# MUX.net
KiCad netlist of a schematic drawn in Altium Designer
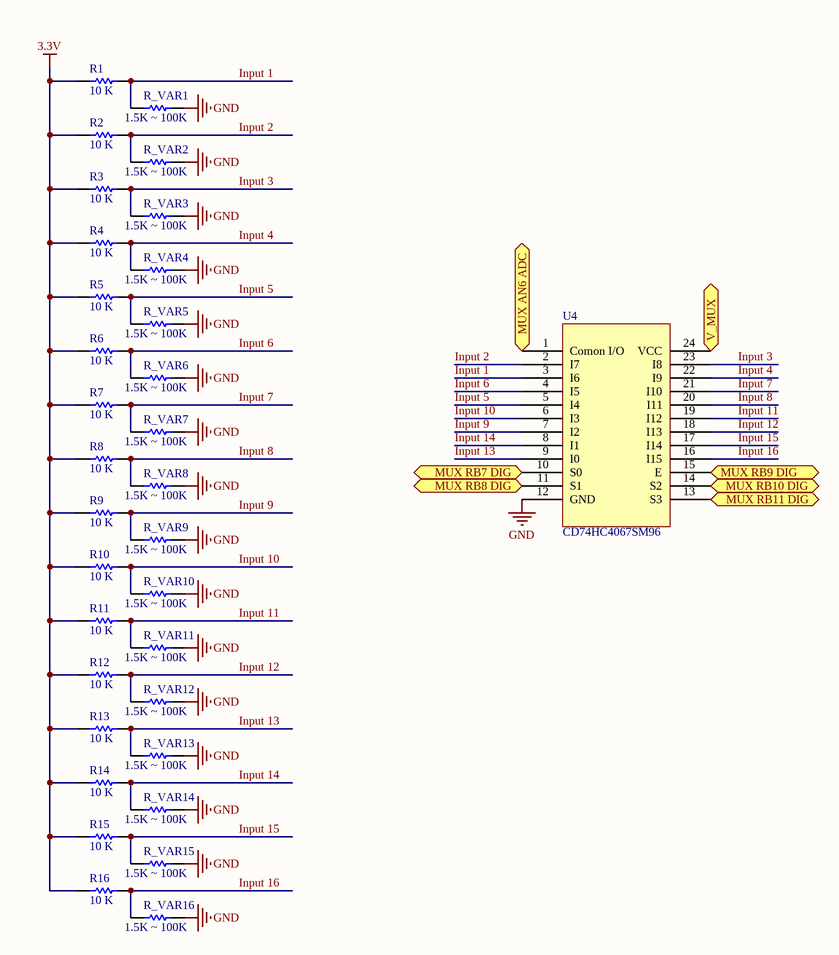
[diagram p0: MUX.SchDoc]

(export (version "E")
  (design (tool "Eeschema 10.0.6"))
  (components
    (comp (ref "R1")
      (value "10 K")
      (footprint "Resistor0603")
      (description "Resistor")
      (fields (field (name "PUBLISHER") "Altium Limited"))
      (libsource (lib "Miscellaneous Devices") (part "Res1"))
    )
    (comp (ref "R2")
      (value "10 K")
      (footprint "Resistor0603")
      (description "Resistor")
      (fields (field (name "PUBLISHER") "Altium Limited"))
      (libsource (lib "Miscellaneous Devices") (part "Res1"))
    )
    (comp (ref "R3")
      (value "10 K")
      (footprint "Resistor0603")
      (description "Resistor")
      (fields (field (name "PUBLISHER") "Altium Limited"))
      (libsource (lib "Miscellaneous Devices") (part "Res1"))
    )
    (comp (ref "R4")
      (value "10 K")
      (footprint "Resistor0603")
      (description "Resistor")
      (fields (field (name "PUBLISHER") "Altium Limited"))
      (libsource (lib "Miscellaneous Devices") (part "Res1"))
    )
    (comp (ref "R5")
      (value "10 K")
      (footprint "Resistor0603")
      (description "Resistor")
      (fields (field (name "PUBLISHER") "Altium Limited"))
      (libsource (lib "Miscellaneous Devices") (part "Res1"))
    )
    (comp (ref "R6")
      (value "10 K")
      (footprint "Resistor0603")
      (description "Resistor")
      (fields (field (name "PUBLISHER") "Altium Limited"))
      (libsource (lib "Miscellaneous Devices") (part "Res1"))
    )
    (comp (ref "R7")
      (value "10 K")
      (footprint "Resistor0603")
      (description "Resistor")
      (fields (field (name "PUBLISHER") "Altium Limited"))
      (libsource (lib "Miscellaneous Devices") (part "Res1"))
    )
    (comp (ref "R8")
      (value "10 K")
      (footprint "Resistor0603")
      (description "Resistor")
      (fields (field (name "PUBLISHER") "Altium Limited"))
      (libsource (lib "Miscellaneous Devices") (part "Res1"))
    )
    (comp (ref "R9")
      (value "10 K")
      (footprint "Resistor0603")
      (description "Resistor")
      (fields (field (name "PUBLISHER") "Altium Limited"))
      (libsource (lib "Miscellaneous Devices") (part "Res1"))
    )
    (comp (ref "R10")
      (value "10 K")
      (footprint "Resistor0603")
      (description "Resistor")
      (fields (field (name "PUBLISHER") "Altium Limited"))
      (libsource (lib "Miscellaneous Devices") (part "Res1"))
    )
    (comp (ref "R11")
      (value "10 K")
      (footprint "Resistor0603")
      (description "Resistor")
      (fields (field (name "PUBLISHER") "Altium Limited"))
      (libsource (lib "Miscellaneous Devices") (part "Res1"))
    )
    (comp (ref "R12")
      (value "10 K")
      (footprint "Resistor0603")
      (description "Resistor")
      (fields (field (name "PUBLISHER") "Altium Limited"))
      (libsource (lib "Miscellaneous Devices") (part "Res1"))
    )
    (comp (ref "R13")
      (value "10 K")
      (footprint "Resistor0603")
      (description "Resistor")
      (fields (field (name "PUBLISHER") "Altium Limited"))
      (libsource (lib "Miscellaneous Devices") (part "Res1"))
    )
    (comp (ref "R14")
      (value "10 K")
      (footprint "Resistor0603")
      (description "Resistor")
      (fields (field (name "PUBLISHER") "Altium Limited"))
      (libsource (lib "Miscellaneous Devices") (part "Res1"))
    )
    (comp (ref "R15")
      (value "10 K")
      (footprint "Resistor0603")
      (description "Resistor")
      (fields (field (name "PUBLISHER") "Altium Limited"))
      (libsource (lib "Miscellaneous Devices") (part "Res1"))
    )
    (comp (ref "R16")
      (value "10 K")
      (footprint "Resistor0603")
      (description "Resistor")
      (fields (field (name "PUBLISHER") "Altium Limited"))
      (libsource (lib "Miscellaneous Devices") (part "Res1"))
    )
    (comp (ref "R_VAR1")
      (value "1.5K ~ 100K")
      (footprint "OrderPiece")
      (description "Resistor")
      (fields (field (name "PUBLISHER") "Altium Limited"))
      (libsource (lib "Miscellaneous Devices") (part "Res1"))
    )
    (comp (ref "R_VAR2")
      (value "1.5K ~ 100K")
      (footprint "OrderPiece")
      (description "Resistor")
      (fields (field (name "PUBLISHER") "Altium Limited"))
      (libsource (lib "Miscellaneous Devices") (part "Res1"))
    )
    (comp (ref "R_VAR3")
      (value "1.5K ~ 100K")
      (footprint "OrderPiece")
      (description "Resistor")
      (fields (field (name "PUBLISHER") "Altium Limited"))
      (libsource (lib "Miscellaneous Devices") (part "Res1"))
    )
    (comp (ref "R_VAR4")
      (value "1.5K ~ 100K")
      (footprint "OrderPiece")
      (description "Resistor")
      (fields (field (name "PUBLISHER") "Altium Limited"))
      (libsource (lib "Miscellaneous Devices") (part "Res1"))
    )
    (comp (ref "R_VAR5")
      (value "1.5K ~ 100K")
      (footprint "OrderPiece")
      (description "Resistor")
      (fields (field (name "PUBLISHER") "Altium Limited"))
      (libsource (lib "Miscellaneous Devices") (part "Res1"))
    )
    (comp (ref "R_VAR6")
      (value "1.5K ~ 100K")
      (footprint "OrderPiece")
      (description "Resistor")
      (fields (field (name "PUBLISHER") "Altium Limited"))
      (libsource (lib "Miscellaneous Devices") (part "Res1"))
    )
    (comp (ref "R_VAR7")
      (value "1.5K ~ 100K")
      (footprint "OrderPiece")
      (description "Resistor")
      (fields (field (name "PUBLISHER") "Altium Limited"))
      (libsource (lib "Miscellaneous Devices") (part "Res1"))
    )
    (comp (ref "R_VAR8")
      (value "1.5K ~ 100K")
      (footprint "OrderPiece")
      (description "Resistor")
      (fields (field (name "PUBLISHER") "Altium Limited"))
      (libsource (lib "Miscellaneous Devices") (part "Res1"))
    )
    (comp (ref "R_VAR9")
      (value "1.5K ~ 100K")
      (footprint "OrderPiece")
      (description "Resistor")
      (fields (field (name "PUBLISHER") "Altium Limited"))
      (libsource (lib "Miscellaneous Devices") (part "Res1"))
    )
    (comp (ref "R_VAR10")
      (value "1.5K ~ 100K")
      (footprint "OrderPiece")
      (description "Resistor")
      (fields (field (name "PUBLISHER") "Altium Limited"))
      (libsource (lib "Miscellaneous Devices") (part "Res1"))
    )
    (comp (ref "R_VAR11")
      (value "1.5K ~ 100K")
      (footprint "OrderPiece")
      (description "Resistor")
      (fields (field (name "PUBLISHER") "Altium Limited"))
      (libsource (lib "Miscellaneous Devices") (part "Res1"))
    )
    (comp (ref "R_VAR12")
      (value "1.5K ~ 100K")
      (footprint "OrderPiece")
      (description "Resistor")
      (fields (field (name "PUBLISHER") "Altium Limited"))
      (libsource (lib "Miscellaneous Devices") (part "Res1"))
    )
    (comp (ref "R_VAR13")
      (value "1.5K ~ 100K")
      (footprint "OrderPiece")
      (description "Resistor")
      (fields (field (name "PUBLISHER") "Altium Limited"))
      (libsource (lib "Miscellaneous Devices") (part "Res1"))
    )
    (comp (ref "R_VAR14")
      (value "1.5K ~ 100K")
      (footprint "OrderPiece")
      (description "Resistor")
      (fields (field (name "PUBLISHER") "Altium Limited"))
      (libsource (lib "Miscellaneous Devices") (part "Res1"))
    )
    (comp (ref "R_VAR15")
      (value "1.5K ~ 100K")
      (footprint "OrderPiece")
      (description "Resistor")
      (fields (field (name "PUBLISHER") "Altium Limited"))
      (libsource (lib "Miscellaneous Devices") (part "Res1"))
    )
    (comp (ref "R_VAR16")
      (value "1.5K ~ 100K")
      (footprint "OrderPiece")
      (description "Resistor")
      (fields (field (name "PUBLISHER") "Altium Limited"))
      (libsource (lib "Miscellaneous Devices") (part "Res1"))
    )
    (comp (ref "U4")
      (value "CD74HC4067SM96")
      (footprint "MUX")
      (libsource (lib "PROBOT_Schema_Library") (part "Analog Multiplexor"))
    )
  )
  (nets
    (net (code "1") (name "/Input 1") (class "Default")
      (node (ref "R1") (pin "2") (pinfunction "2_2") (pintype "passive"))
      (node (ref "R_VAR1") (pin "1") (pinfunction "1_1") (pintype "passive"))
      (node (ref "U4") (pin "3") (pinfunction "I6_3") (pintype "passive"))
    )
    (net (code "2") (name "/Input 2") (class "Default")
      (node (ref "R2") (pin "2") (pinfunction "2_2") (pintype "passive"))
      (node (ref "R_VAR2") (pin "1") (pinfunction "1_1") (pintype "passive"))
      (node (ref "U4") (pin "2") (pinfunction "I7_2") (pintype "passive"))
    )
    (net (code "3") (name "/Input 3") (class "Default")
      (node (ref "R3") (pin "2") (pinfunction "2_2") (pintype "passive"))
      (node (ref "R_VAR3") (pin "1") (pinfunction "1_1") (pintype "passive"))
      (node (ref "U4") (pin "23") (pinfunction "I8_23") (pintype "passive"))
    )
    (net (code "4") (name "/Input 4") (class "Default")
      (node (ref "R4") (pin "2") (pinfunction "2_2") (pintype "passive"))
      (node (ref "R_VAR4") (pin "1") (pinfunction "1_1") (pintype "passive"))
      (node (ref "U4") (pin "22") (pinfunction "I9_22") (pintype "passive"))
    )
    (net (code "5") (name "/Input 5") (class "Default")
      (node (ref "R5") (pin "2") (pinfunction "2_2") (pintype "passive"))
      (node (ref "R_VAR5") (pin "1") (pinfunction "1_1") (pintype "passive"))
      (node (ref "U4") (pin "5") (pinfunction "I4_5") (pintype "passive"))
    )
    (net (code "6") (name "/Input 6") (class "Default")
      (node (ref "R6") (pin "2") (pinfunction "2_2") (pintype "passive"))
      (node (ref "R_VAR6") (pin "1") (pinfunction "1_1") (pintype "passive"))
      (node (ref "U4") (pin "4") (pinfunction "I5_4") (pintype "passive"))
    )
    (net (code "7") (name "/Input 7") (class "Default")
      (node (ref "R7") (pin "2") (pinfunction "2_2") (pintype "passive"))
      (node (ref "R_VAR7") (pin "1") (pinfunction "1_1") (pintype "passive"))
      (node (ref "U4") (pin "21") (pinfunction "I10_21") (pintype "passive"))
    )
    (net (code "8") (name "/Input 8") (class "Default")
      (node (ref "R8") (pin "2") (pinfunction "2_2") (pintype "passive"))
      (node (ref "R_VAR8") (pin "1") (pinfunction "1_1") (pintype "passive"))
      (node (ref "U4") (pin "20") (pinfunction "I11_20") (pintype "passive"))
    )
    (net (code "9") (name "/Input 9") (class "Default")
      (node (ref "R9") (pin "2") (pinfunction "2_2") (pintype "passive"))
      (node (ref "R_VAR9") (pin "1") (pinfunction "1_1") (pintype "passive"))
      (node (ref "U4") (pin "7") (pinfunction "I2_7") (pintype "passive"))
    )
    (net (code "10") (name "/Input 10") (class "Default")
      (node (ref "R10") (pin "2") (pinfunction "2_2") (pintype "passive"))
      (node (ref "R_VAR10") (pin "1") (pinfunction "1_1") (pintype "passive"))
      (node (ref "U4") (pin "6") (pinfunction "I3_6") (pintype "passive"))
    )
    (net (code "11") (name "/Input 11") (class "Default")
      (node (ref "R11") (pin "2") (pinfunction "2_2") (pintype "passive"))
      (node (ref "R_VAR11") (pin "1") (pinfunction "1_1") (pintype "passive"))
      (node (ref "U4") (pin "19") (pinfunction "I12_19") (pintype "passive"))
    )
    (net (code "12") (name "/Input 12") (class "Default")
      (node (ref "R12") (pin "2") (pinfunction "2_2") (pintype "passive"))
      (node (ref "R_VAR12") (pin "1") (pinfunction "1_1") (pintype "passive"))
      (node (ref "U4") (pin "18") (pinfunction "I13_18") (pintype "passive"))
    )
    (net (code "13") (name "/Input 13") (class "Default")
      (node (ref "R13") (pin "2") (pinfunction "2_2") (pintype "passive"))
      (node (ref "R_VAR13") (pin "1") (pinfunction "1_1") (pintype "passive"))
      (node (ref "U4") (pin "9") (pinfunction "I0_9") (pintype "passive"))
    )
    (net (code "14") (name "/Input 14") (class "Default")
      (node (ref "R14") (pin "2") (pinfunction "2_2") (pintype "passive"))
      (node (ref "R_VAR14") (pin "1") (pinfunction "1_1") (pintype "passive"))
      (node (ref "U4") (pin "8") (pinfunction "I1_8") (pintype "passive"))
    )
    (net (code "15") (name "/Input 15") (class "Default")
      (node (ref "R15") (pin "2") (pinfunction "2_2") (pintype "passive"))
      (node (ref "R_VAR15") (pin "1") (pinfunction "1_1") (pintype "passive"))
      (node (ref "U4") (pin "17") (pinfunction "I14_17") (pintype "passive"))
    )
    (net (code "16") (name "/Input 16") (class "Default")
      (node (ref "R16") (pin "2") (pinfunction "2_2") (pintype "passive"))
      (node (ref "R_VAR16") (pin "1") (pinfunction "1_1") (pintype "passive"))
      (node (ref "U4") (pin "16") (pinfunction "I15_16") (pintype "passive"))
    )
    (net (code "17") (name "/MUX AN6 ADC") (class "Default")
      (node (ref "U4") (pin "1") (pinfunction "Comon_I/O_1") (pintype "passive"))
    )
    (net (code "18") (name "/MUX RB7 DIG") (class "Default")
      (node (ref "U4") (pin "10") (pinfunction "S0_10") (pintype "passive"))
    )
    (net (code "19") (name "/MUX RB8 DIG") (class "Default")
      (node (ref "U4") (pin "11") (pinfunction "S1_11") (pintype "passive"))
    )
    (net (code "20") (name "/MUX RB9 DIG") (class "Default")
      (node (ref "U4") (pin "15") (pinfunction "E_15") (pintype "passive"))
    )
    (net (code "21") (name "/MUX RB10 DIG") (class "Default")
      (node (ref "U4") (pin "14") (pinfunction "S2_14") (pintype "passive"))
    )
    (net (code "22") (name "/MUX RB11 DIG") (class "Default")
      (node (ref "U4") (pin "13") (pinfunction "S3_13") (pintype "passive"))
    )
    (net (code "23") (name "/V_MUX") (class "Default")
      (node (ref "U4") (pin "24") (pinfunction "VCC_24") (pintype "passive"))
    )
    (net (code "24") (name "3.3V") (class "Default")
      (node (ref "R1") (pin "1") (pinfunction "1_1") (pintype "passive"))
      (node (ref "R10") (pin "1") (pinfunction "1_1") (pintype "passive"))
      (node (ref "R11") (pin "1") (pinfunction "1_1") (pintype "passive"))
      (node (ref "R12") (pin "1") (pinfunction "1_1") (pintype "passive"))
      (node (ref "R13") (pin "1") (pinfunction "1_1") (pintype "passive"))
      (node (ref "R14") (pin "1") (pinfunction "1_1") (pintype "passive"))
      (node (ref "R15") (pin "1") (pinfunction "1_1") (pintype "passive"))
      (node (ref "R16") (pin "1") (pinfunction "1_1") (pintype "passive"))
      (node (ref "R2") (pin "1") (pinfunction "1_1") (pintype "passive"))
      (node (ref "R3") (pin "1") (pinfunction "1_1") (pintype "passive"))
      (node (ref "R4") (pin "1") (pinfunction "1_1") (pintype "passive"))
      (node (ref "R5") (pin "1") (pinfunction "1_1") (pintype "passive"))
      (node (ref "R6") (pin "1") (pinfunction "1_1") (pintype "passive"))
      (node (ref "R7") (pin "1") (pinfunction "1_1") (pintype "passive"))
      (node (ref "R8") (pin "1") (pinfunction "1_1") (pintype "passive"))
      (node (ref "R9") (pin "1") (pinfunction "1_1") (pintype "passive"))
    )
    (net (code "25") (name "GND") (class "Default")
      (node (ref "R_VAR1") (pin "2") (pinfunction "2_2") (pintype "passive"))
      (node (ref "R_VAR10") (pin "2") (pinfunction "2_2") (pintype "passive"))
      (node (ref "R_VAR11") (pin "2") (pinfunction "2_2") (pintype "passive"))
      (node (ref "R_VAR12") (pin "2") (pinfunction "2_2") (pintype "passive"))
      (node (ref "R_VAR13") (pin "2") (pinfunction "2_2") (pintype "passive"))
      (node (ref "R_VAR14") (pin "2") (pinfunction "2_2") (pintype "passive"))
      (node (ref "R_VAR15") (pin "2") (pinfunction "2_2") (pintype "passive"))
      (node (ref "R_VAR16") (pin "2") (pinfunction "2_2") (pintype "passive"))
      (node (ref "R_VAR2") (pin "2") (pinfunction "2_2") (pintype "passive"))
      (node (ref "R_VAR3") (pin "2") (pinfunction "2_2") (pintype "passive"))
      (node (ref "R_VAR4") (pin "2") (pinfunction "2_2") (pintype "passive"))
      (node (ref "R_VAR5") (pin "2") (pinfunction "2_2") (pintype "passive"))
      (node (ref "R_VAR6") (pin "2") (pinfunction "2_2") (pintype "passive"))
      (node (ref "R_VAR7") (pin "2") (pinfunction "2_2") (pintype "passive"))
      (node (ref "R_VAR8") (pin "2") (pinfunction "2_2") (pintype "passive"))
      (node (ref "R_VAR9") (pin "2") (pinfunction "2_2") (pintype "passive"))
      (node (ref "U4") (pin "12") (pinfunction "GND_12") (pintype "passive"))
    )
  )
)
